# Accelerometer.net
KiCad netlist of a schematic drawn in Altium Designer
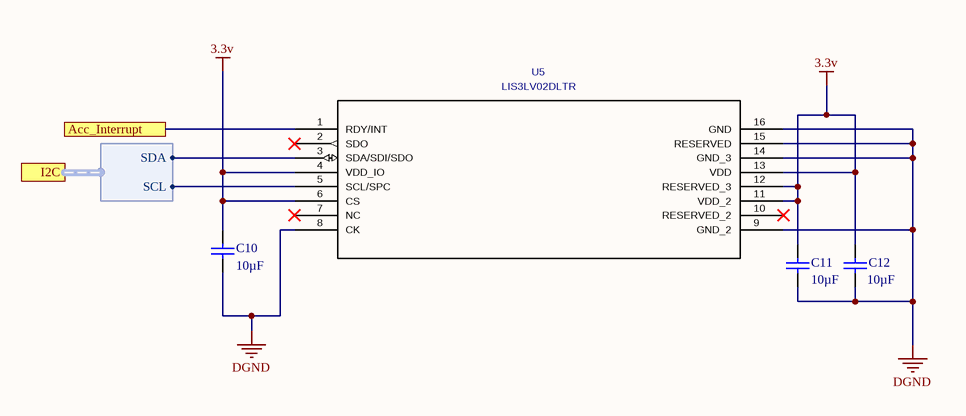
[diagram p0: Accelerometer.SchDoc]

(export (version "E")
  (design (tool "Eeschema 10.0.6"))
  (components
    (comp (ref "C10")
      (value "C1608X5R1A106K080AC")
      (footprint "CAPC1608X90X20LL10")
      (description "Chip Capacitor, 10 uF, +/- 10%, 10 V, -55 to 85 degC, 0603 (1608 Metric), RoHS, Tape and Reel")
      (fields
        (field (name "PCN PART NUMBER") "MLCCPartNumberChange30/Nov/2012")
        (field (name "CAPACITANCE") "10µF")
        (field (name "TOLERANCE") "±10%")
      )
      (libsource (lib "Passives") (part "CMP-2000-04979-1"))
    )
    (comp (ref "C11")
      (value "C1608X5R1A106K080AC")
      (footprint "CAPC1608X90X20LL10")
      (description "Chip Capacitor, 10 uF, +/- 10%, 10 V, -55 to 85 degC, 0603 (1608 Metric), RoHS, Tape and Reel")
      (fields
        (field (name "PCN PART NUMBER") "MLCCPartNumberChange30/Nov/2012")
        (field (name "CAPACITANCE") "10µF")
        (field (name "TOLERANCE") "±10%")
      )
      (libsource (lib "Passives") (part "CMP-2000-04979-1"))
    )
    (comp (ref "C12")
      (value "C1608X5R1A106K080AC")
      (footprint "CAPC1608X90X20LL10")
      (description "Chip Capacitor, 10 uF, +/- 10%, 10 V, -55 to 85 degC, 0603 (1608 Metric), RoHS, Tape and Reel")
      (fields
        (field (name "PCN PART NUMBER") "MLCCPartNumberChange30/Nov/2012")
        (field (name "CAPACITANCE") "10µF")
        (field (name "TOLERANCE") "±10%")
      )
      (libsource (lib "Passives") (part "CMP-2000-04979-1"))
    )
    (comp (ref "U5")
      (value "LIS3LV02DLTR")
      (footprint "LGA-16_4P4X7P5X1")
      (description "ACCELEROMETER 2-6G I2C/SPI 16LGA")
      (libsource (lib "Components") (part "LIS3LV02DLTR"))
    )
  )
  (nets
    (net (code "2") (name "/Acc_Interrupt") (class "Default")
      (node (ref "U5") (pin "1") (pinfunction "RDY/INT_1") (pintype "passive"))
    )
    (net (code "3") (name "/SCL") (class "Default")
      (node (ref "U5") (pin "5") (pinfunction "SCL/SPC_5") (pintype "passive"))
    )
    (net (code "4") (name "/SDA") (class "Default")
      (node (ref "U5") (pin "3") (pinfunction "SDA/SDI/SDO_3") (pintype "bidirectional"))
    )
    (net (code "6") (name "3.3v") (class "Default")
      (node (ref "C10") (pin "2") (pinfunction "2_2") (pintype "passive"))
      (node (ref "C11") (pin "2") (pinfunction "2_2") (pintype "passive"))
      (node (ref "C12") (pin "2") (pinfunction "2_2") (pintype "passive"))
      (node (ref "U5") (pin "11") (pinfunction "VDD_2_11") (pintype "power_in"))
      (node (ref "U5") (pin "12") (pinfunction "RESERVED_3_12") (pintype "passive"))
      (node (ref "U5") (pin "13") (pinfunction "VDD_13") (pintype "power_in"))
      (node (ref "U5") (pin "4") (pinfunction "VDD_IO_4") (pintype "power_in"))
      (node (ref "U5") (pin "6") (pinfunction "CS_6") (pintype "passive"))
    )
    (net (code "7") (name "DGND") (class "Default")
      (node (ref "C10") (pin "1") (pinfunction "1_1") (pintype "passive"))
      (node (ref "C11") (pin "1") (pinfunction "1_1") (pintype "passive"))
      (node (ref "C12") (pin "1") (pinfunction "1_1") (pintype "passive"))
      (node (ref "U5") (pin "14") (pinfunction "GND_3_14") (pintype "power_in"))
      (node (ref "U5") (pin "15") (pinfunction "RESERVED_15") (pintype "passive"))
      (node (ref "U5") (pin "16") (pinfunction "GND_16") (pintype "power_in"))
      (node (ref "U5") (pin "8") (pinfunction "CK_8") (pintype "passive"))
      (node (ref "U5") (pin "9") (pinfunction "GND_2_9") (pintype "power_in"))
    )
    (net (code "8") (name "unconnected-(U5-NC-Pad7)") (class "Default")
      (node (ref "U5") (pin "7") (pinfunction "NC_7") (pintype "passive+no_connect"))
    )
    (net (code "9") (name "unconnected-(U5-RESERVED_2-Pad10)") (class "Default")
      (node (ref "U5") (pin "10") (pinfunction "RESERVED_2_10") (pintype "passive+no_connect"))
    )
    (net (code "10") (name "unconnected-(U5-SDO-Pad2)") (class "Default")
      (node (ref "U5") (pin "2") (pinfunction "SDO_2") (pintype "output+no_connect"))
    )
  )
)
